# VNH9013Y.net
KiCad netlist of a schematic drawn in Altium Designer
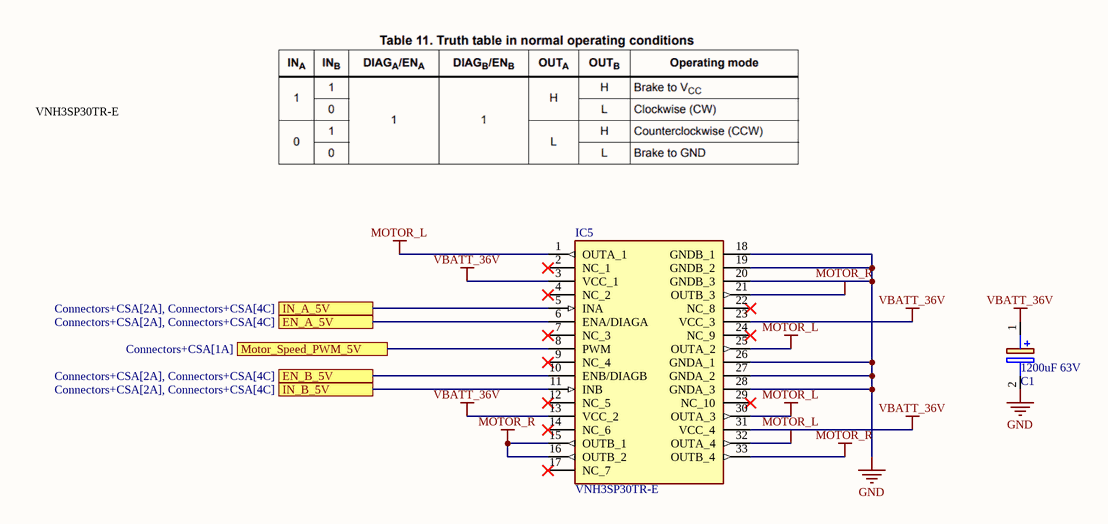
[diagram p0: VNH9013Y.SchDoc]

(export (version "E")
  (design (tool "Eeschema 10.0.6"))
  (components
    (comp (ref "C1")
      (value "1200uF 63V")
      (footprint "SamacSys:CAPPRD750W80D1825H3750")
      (description "Capacitor Polarised")
      (fields
        (field (name "MANUFACTURER_PART_NUMBER") "UHE1J122MHD6")
        (field (name "MOUSER PART NUMBER") "647-UHE1J122MHD6")
      )
      (libsource (lib "*") (part "UHE1J122MHD6"))
    )
    (comp (ref "IC5")
      (value "VNH3SP30TR-E")
      (footprint "SamacSys:MULTIPOWERSO-30")
      (description "Integrated Circuit")
      (fields (field (name "MOUSER PART NUMBER") "511-VNH3SP30TR-E"))
      (libsource (lib "*") (part "VNH3SP30TR-E"))
    )
  )
  (nets
    (net (code "1") (name "/EN_A_5V") (class "Default")
      (node (ref "IC5") (pin "6") (pinfunction "ENA/DIAGA_6") (pintype "passive"))
    )
    (net (code "2") (name "/EN_B_5V") (class "Default")
      (node (ref "IC5") (pin "10") (pinfunction "ENB/DIAGB_10") (pintype "passive"))
    )
    (net (code "3") (name "/IN_A_5V") (class "Default")
      (node (ref "IC5") (pin "5") (pinfunction "INA_5") (pintype "input"))
    )
    (net (code "4") (name "/IN_B_5V") (class "Default")
      (node (ref "IC5") (pin "11") (pinfunction "INB_11") (pintype "input"))
    )
    (net (code "5") (name "/Motor_Speed_PWM_5V") (class "Default")
      (node (ref "IC5") (pin "8") (pinfunction "PWM_8") (pintype "passive"))
    )
    (net (code "6") (name "GND") (class "Default")
      (node (ref "C1") (pin "2") (pinfunction "-_2") (pintype "passive"))
      (node (ref "IC5") (pin "18") (pinfunction "GNDB_1_18") (pintype "power_in"))
      (node (ref "IC5") (pin "19") (pinfunction "GNDB_2_19") (pintype "power_in"))
      (node (ref "IC5") (pin "20") (pinfunction "GNDB_3_20") (pintype "power_in"))
      (node (ref "IC5") (pin "26") (pinfunction "GNDA_1_26") (pintype "power_in"))
      (node (ref "IC5") (pin "27") (pinfunction "GNDA_2_27") (pintype "power_in"))
      (node (ref "IC5") (pin "28") (pinfunction "GNDA_3_28") (pintype "power_in"))
    )
    (net (code "7") (name "MOTOR_L") (class "Default")
      (node (ref "IC5") (pin "1") (pinfunction "OUTA_1_1") (pintype "output"))
      (node (ref "IC5") (pin "25") (pinfunction "OUTA_2_25") (pintype "output"))
      (node (ref "IC5") (pin "30") (pinfunction "OUTA_3_30") (pintype "output"))
      (node (ref "IC5") (pin "32") (pinfunction "OUTA_4_32") (pintype "output"))
    )
    (net (code "8") (name "MOTOR_R") (class "Default")
      (node (ref "IC5") (pin "15") (pinfunction "OUTB_1_15") (pintype "output"))
      (node (ref "IC5") (pin "16") (pinfunction "OUTB_2_16") (pintype "output"))
      (node (ref "IC5") (pin "21") (pinfunction "OUTB_3_21") (pintype "output"))
      (node (ref "IC5") (pin "33") (pinfunction "OUTB_4_33") (pintype "output"))
    )
    (net (code "9") (name "VBATT_36V") (class "Default")
      (node (ref "C1") (pin "1") (pinfunction "+_1") (pintype "passive"))
      (node (ref "IC5") (pin "13") (pinfunction "VCC_2_13") (pintype "power_in"))
      (node (ref "IC5") (pin "23") (pinfunction "VCC_3_23") (pintype "power_in"))
      (node (ref "IC5") (pin "3") (pinfunction "VCC_1_3") (pintype "power_in"))
      (node (ref "IC5") (pin "31") (pinfunction "VCC_4_31") (pintype "power_in"))
    )
    (net (code "10") (name "unconnected-(IC5-NC_1-Pad2)") (class "Default")
      (node (ref "IC5") (pin "2") (pinfunction "NC_1_2") (pintype "passive+no_connect"))
    )
    (net (code "11") (name "unconnected-(IC5-NC_2-Pad4)") (class "Default")
      (node (ref "IC5") (pin "4") (pinfunction "NC_2_4") (pintype "passive+no_connect"))
    )
    (net (code "12") (name "unconnected-(IC5-NC_3-Pad7)") (class "Default")
      (node (ref "IC5") (pin "7") (pinfunction "NC_3_7") (pintype "passive+no_connect"))
    )
    (net (code "13") (name "unconnected-(IC5-NC_4-Pad9)") (class "Default")
      (node (ref "IC5") (pin "9") (pinfunction "NC_4_9") (pintype "passive+no_connect"))
    )
    (net (code "14") (name "unconnected-(IC5-NC_5-Pad12)") (class "Default")
      (node (ref "IC5") (pin "12") (pinfunction "NC_5_12") (pintype "passive+no_connect"))
    )
    (net (code "15") (name "unconnected-(IC5-NC_6-Pad14)") (class "Default")
      (node (ref "IC5") (pin "14") (pinfunction "NC_6_14") (pintype "passive+no_connect"))
    )
    (net (code "16") (name "unconnected-(IC5-NC_7-Pad17)") (class "Default")
      (node (ref "IC5") (pin "17") (pinfunction "NC_7_17") (pintype "passive+no_connect"))
    )
    (net (code "17") (name "unconnected-(IC5-NC_8-Pad22)") (class "Default")
      (node (ref "IC5") (pin "22") (pinfunction "NC_8_22") (pintype "passive+no_connect"))
    )
    (net (code "18") (name "unconnected-(IC5-NC_9-Pad24)") (class "Default")
      (node (ref "IC5") (pin "24") (pinfunction "NC_9_24") (pintype "passive+no_connect"))
    )
    (net (code "19") (name "unconnected-(IC5-NC_10-Pad29)") (class "Default")
      (node (ref "IC5") (pin "29") (pinfunction "NC_10_29") (pintype "passive+no_connect"))
    )
  )
)
